# LED.net
KiCad netlist of a schematic drawn in Altium Designer
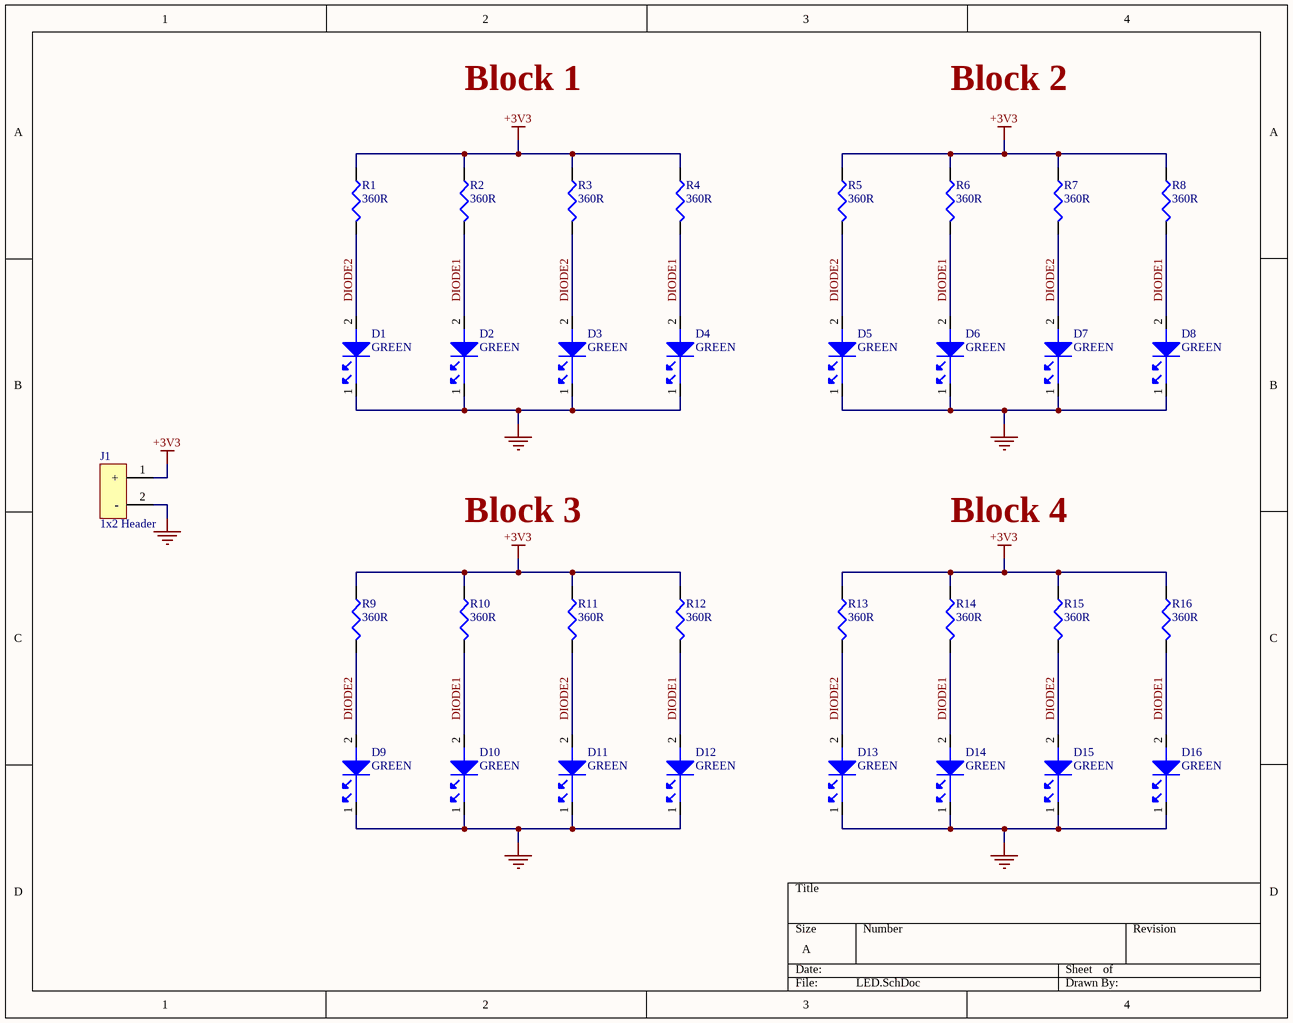
[diagram p0: LED.SchDoc]

(export (version "E")
  (design (tool "Eeschema 10.0.6"))
  (components
    (comp (ref "D1")
      (value "GREEN")
      (footprint "LED0603G")
      (description "Standard LEDs - SMD LED GR HI-BRT USS")
      (fields
        (field (name "MANUFACTURER") "Panasonic SSG")
        (field (name "MANUFACTURER PART NUMBER") "LNJ337W83RA")
      )
      (libsource (lib "LED_SchLib") (part "LNJ337W83RA"))
    )
    (comp (ref "D2")
      (value "GREEN")
      (footprint "LED0603G")
      (description "Standard LEDs - SMD LED GR HI-BRT USS")
      (fields
        (field (name "MANUFACTURER") "Panasonic SSG")
        (field (name "MANUFACTURER PART NUMBER") "LNJ337W83RA")
      )
      (libsource (lib "LED_SchLib") (part "LNJ337W83RA"))
    )
    (comp (ref "D3")
      (value "GREEN")
      (footprint "LED0603G")
      (description "Standard LEDs - SMD LED GR HI-BRT USS")
      (fields
        (field (name "MANUFACTURER") "Panasonic SSG")
        (field (name "MANUFACTURER PART NUMBER") "LNJ337W83RA")
      )
      (libsource (lib "LED_SchLib") (part "LNJ337W83RA"))
    )
    (comp (ref "D4")
      (value "GREEN")
      (footprint "LED0603G")
      (description "Standard LEDs - SMD LED GR HI-BRT USS")
      (fields
        (field (name "MANUFACTURER") "Panasonic SSG")
        (field (name "MANUFACTURER PART NUMBER") "LNJ337W83RA")
      )
      (libsource (lib "LED_SchLib") (part "LNJ337W83RA"))
    )
    (comp (ref "D5")
      (value "GREEN")
      (footprint "LED0603G")
      (description "Standard LEDs - SMD LED GR HI-BRT USS")
      (fields
        (field (name "MANUFACTURER") "Panasonic SSG")
        (field (name "MANUFACTURER PART NUMBER") "LNJ337W83RA")
      )
      (libsource (lib "LED_SchLib") (part "LNJ337W83RA"))
    )
    (comp (ref "D6")
      (value "GREEN")
      (footprint "LED0603G")
      (description "Standard LEDs - SMD LED GR HI-BRT USS")
      (fields
        (field (name "MANUFACTURER") "Panasonic SSG")
        (field (name "MANUFACTURER PART NUMBER") "LNJ337W83RA")
      )
      (libsource (lib "LED_SchLib") (part "LNJ337W83RA"))
    )
    (comp (ref "D7")
      (value "GREEN")
      (footprint "LED0603G")
      (description "Standard LEDs - SMD LED GR HI-BRT USS")
      (fields
        (field (name "MANUFACTURER") "Panasonic SSG")
        (field (name "MANUFACTURER PART NUMBER") "LNJ337W83RA")
      )
      (libsource (lib "LED_SchLib") (part "LNJ337W83RA"))
    )
    (comp (ref "D8")
      (value "GREEN")
      (footprint "LED0603G")
      (description "Standard LEDs - SMD LED GR HI-BRT USS")
      (fields
        (field (name "MANUFACTURER") "Panasonic SSG")
        (field (name "MANUFACTURER PART NUMBER") "LNJ337W83RA")
      )
      (libsource (lib "LED_SchLib") (part "LNJ337W83RA"))
    )
    (comp (ref "D9")
      (value "GREEN")
      (footprint "LED0603G")
      (description "Standard LEDs - SMD LED GR HI-BRT USS")
      (fields
        (field (name "MANUFACTURER") "Panasonic SSG")
        (field (name "MANUFACTURER PART NUMBER") "LNJ337W83RA")
      )
      (libsource (lib "LED_SchLib") (part "LNJ337W83RA"))
    )
    (comp (ref "D10")
      (value "GREEN")
      (footprint "LED0603G")
      (description "Standard LEDs - SMD LED GR HI-BRT USS")
      (fields
        (field (name "MANUFACTURER") "Panasonic SSG")
        (field (name "MANUFACTURER PART NUMBER") "LNJ337W83RA")
      )
      (libsource (lib "LED_SchLib") (part "LNJ337W83RA"))
    )
    (comp (ref "D11")
      (value "GREEN")
      (footprint "LED0603G")
      (description "Standard LEDs - SMD LED GR HI-BRT USS")
      (fields
        (field (name "MANUFACTURER") "Panasonic SSG")
        (field (name "MANUFACTURER PART NUMBER") "LNJ337W83RA")
      )
      (libsource (lib "LED_SchLib") (part "LNJ337W83RA"))
    )
    (comp (ref "D12")
      (value "GREEN")
      (footprint "LED0603G")
      (description "Standard LEDs - SMD LED GR HI-BRT USS")
      (fields
        (field (name "MANUFACTURER") "Panasonic SSG")
        (field (name "MANUFACTURER PART NUMBER") "LNJ337W83RA")
      )
      (libsource (lib "LED_SchLib") (part "LNJ337W83RA"))
    )
    (comp (ref "D13")
      (value "GREEN")
      (footprint "LED0603G")
      (description "Standard LEDs - SMD LED GR HI-BRT USS")
      (fields
        (field (name "MANUFACTURER") "Panasonic SSG")
        (field (name "MANUFACTURER PART NUMBER") "LNJ337W83RA")
      )
      (libsource (lib "LED_SchLib") (part "LNJ337W83RA"))
    )
    (comp (ref "D14")
      (value "GREEN")
      (footprint "LED0603G")
      (description "Standard LEDs - SMD LED GR HI-BRT USS")
      (fields
        (field (name "MANUFACTURER") "Panasonic SSG")
        (field (name "MANUFACTURER PART NUMBER") "LNJ337W83RA")
      )
      (libsource (lib "LED_SchLib") (part "LNJ337W83RA"))
    )
    (comp (ref "D15")
      (value "GREEN")
      (footprint "LED0603G")
      (description "Standard LEDs - SMD LED GR HI-BRT USS")
      (fields
        (field (name "MANUFACTURER") "Panasonic SSG")
        (field (name "MANUFACTURER PART NUMBER") "LNJ337W83RA")
      )
      (libsource (lib "LED_SchLib") (part "LNJ337W83RA"))
    )
    (comp (ref "D16")
      (value "GREEN")
      (footprint "LED0603G")
      (description "Standard LEDs - SMD LED GR HI-BRT USS")
      (fields
        (field (name "MANUFACTURER") "Panasonic SSG")
        (field (name "MANUFACTURER PART NUMBER") "LNJ337W83RA")
      )
      (libsource (lib "LED_SchLib") (part "LNJ337W83RA"))
    )
    (comp (ref "J1")
      (value "1x2 Header")
      (footprint "HDR1X2")
      (description "Headers & Wire Housings 2 PIN F/LK HEADER")
      (fields (field (name "MANUFACTURER") "Molex") (field (name "MANUFACTURER PART NUMBER") "22-29-2021"))
      (libsource (lib "LED_SchLib") (part "22-29-2021"))
    )
    (comp (ref "R1")
      (value "360R")
      (footprint "R0805")
      (description "RES SMD 360 OHM 1% 1/8W 0805")
      (fields
        (field (name "MANUFACTURER") "Vishay")
        (field (name "MANUFACTURER PART NUMBER") "CRCW0805360RFKEA")
      )
      (libsource (lib "LED_SchLib") (part "CRCW0805360RFKEA"))
    )
    (comp (ref "R2")
      (value "360R")
      (footprint "R0805")
      (description "RES SMD 360 OHM 1% 1/8W 0805")
      (fields
        (field (name "MANUFACTURER") "Vishay")
        (field (name "MANUFACTURER PART NUMBER") "CRCW0805360RFKEA")
      )
      (libsource (lib "LED_SchLib") (part "CRCW0805360RFKEA"))
    )
    (comp (ref "R3")
      (value "360R")
      (footprint "R0805")
      (description "RES SMD 360 OHM 1% 1/8W 0805")
      (fields
        (field (name "MANUFACTURER") "Vishay")
        (field (name "MANUFACTURER PART NUMBER") "CRCW0805360RFKEA")
      )
      (libsource (lib "LED_SchLib") (part "CRCW0805360RFKEA"))
    )
    (comp (ref "R4")
      (value "360R")
      (footprint "R0805")
      (description "RES SMD 360 OHM 1% 1/8W 0805")
      (fields
        (field (name "MANUFACTURER") "Vishay")
        (field (name "MANUFACTURER PART NUMBER") "CRCW0805360RFKEA")
      )
      (libsource (lib "LED_SchLib") (part "CRCW0805360RFKEA"))
    )
    (comp (ref "R5")
      (value "360R")
      (footprint "R0805")
      (description "RES SMD 360 OHM 1% 1/8W 0805")
      (fields
        (field (name "MANUFACTURER") "Vishay")
        (field (name "MANUFACTURER PART NUMBER") "CRCW0805360RFKEA")
      )
      (libsource (lib "LED_SchLib") (part "CRCW0805360RFKEA"))
    )
    (comp (ref "R6")
      (value "360R")
      (footprint "R0805")
      (description "RES SMD 360 OHM 1% 1/8W 0805")
      (fields
        (field (name "MANUFACTURER") "Vishay")
        (field (name "MANUFACTURER PART NUMBER") "CRCW0805360RFKEA")
      )
      (libsource (lib "LED_SchLib") (part "CRCW0805360RFKEA"))
    )
    (comp (ref "R7")
      (value "360R")
      (footprint "R0805")
      (description "RES SMD 360 OHM 1% 1/8W 0805")
      (fields
        (field (name "MANUFACTURER") "Vishay")
        (field (name "MANUFACTURER PART NUMBER") "CRCW0805360RFKEA")
      )
      (libsource (lib "LED_SchLib") (part "CRCW0805360RFKEA"))
    )
    (comp (ref "R8")
      (value "360R")
      (footprint "R0805")
      (description "RES SMD 360 OHM 1% 1/8W 0805")
      (fields
        (field (name "MANUFACTURER") "Vishay")
        (field (name "MANUFACTURER PART NUMBER") "CRCW0805360RFKEA")
      )
      (libsource (lib "LED_SchLib") (part "CRCW0805360RFKEA"))
    )
    (comp (ref "R9")
      (value "360R")
      (footprint "R0805")
      (description "RES SMD 360 OHM 1% 1/8W 0805")
      (fields
        (field (name "MANUFACTURER") "Vishay")
        (field (name "MANUFACTURER PART NUMBER") "CRCW0805360RFKEA")
      )
      (libsource (lib "LED_SchLib") (part "CRCW0805360RFKEA"))
    )
    (comp (ref "R10")
      (value "360R")
      (footprint "R0805")
      (description "RES SMD 360 OHM 1% 1/8W 0805")
      (fields
        (field (name "MANUFACTURER") "Vishay")
        (field (name "MANUFACTURER PART NUMBER") "CRCW0805360RFKEA")
      )
      (libsource (lib "LED_SchLib") (part "CRCW0805360RFKEA"))
    )
    (comp (ref "R11")
      (value "360R")
      (footprint "R0805")
      (description "RES SMD 360 OHM 1% 1/8W 0805")
      (fields
        (field (name "MANUFACTURER") "Vishay")
        (field (name "MANUFACTURER PART NUMBER") "CRCW0805360RFKEA")
      )
      (libsource (lib "LED_SchLib") (part "CRCW0805360RFKEA"))
    )
    (comp (ref "R12")
      (value "360R")
      (footprint "R0805")
      (description "RES SMD 360 OHM 1% 1/8W 0805")
      (fields
        (field (name "MANUFACTURER") "Vishay")
        (field (name "MANUFACTURER PART NUMBER") "CRCW0805360RFKEA")
      )
      (libsource (lib "LED_SchLib") (part "CRCW0805360RFKEA"))
    )
    (comp (ref "R13")
      (value "360R")
      (footprint "R0805")
      (description "RES SMD 360 OHM 1% 1/8W 0805")
      (fields
        (field (name "MANUFACTURER") "Vishay")
        (field (name "MANUFACTURER PART NUMBER") "CRCW0805360RFKEA")
      )
      (libsource (lib "LED_SchLib") (part "CRCW0805360RFKEA"))
    )
    (comp (ref "R14")
      (value "360R")
      (footprint "R0805")
      (description "RES SMD 360 OHM 1% 1/8W 0805")
      (fields
        (field (name "MANUFACTURER") "Vishay")
        (field (name "MANUFACTURER PART NUMBER") "CRCW0805360RFKEA")
      )
      (libsource (lib "LED_SchLib") (part "CRCW0805360RFKEA"))
    )
    (comp (ref "R15")
      (value "360R")
      (footprint "R0805")
      (description "RES SMD 360 OHM 1% 1/8W 0805")
      (fields
        (field (name "MANUFACTURER") "Vishay")
        (field (name "MANUFACTURER PART NUMBER") "CRCW0805360RFKEA")
      )
      (libsource (lib "LED_SchLib") (part "CRCW0805360RFKEA"))
    )
    (comp (ref "R16")
      (value "360R")
      (footprint "R0805")
      (description "RES SMD 360 OHM 1% 1/8W 0805")
      (fields
        (field (name "MANUFACTURER") "Vishay")
        (field (name "MANUFACTURER PART NUMBER") "CRCW0805360RFKEA")
      )
      (libsource (lib "LED_SchLib") (part "CRCW0805360RFKEA"))
    )
  )
  (nets
    (net (code "1") (name "+3V3") (class "Default")
      (node (ref "J1") (pin "1") (pinfunction "+_1") (pintype "passive"))
      (node (ref "R1") (pin "1") (pinfunction "1_1") (pintype "passive"))
      (node (ref "R10") (pin "1") (pinfunction "1_1") (pintype "passive"))
      (node (ref "R11") (pin "1") (pinfunction "1_1") (pintype "passive"))
      (node (ref "R12") (pin "1") (pinfunction "1_1") (pintype "passive"))
      (node (ref "R13") (pin "1") (pinfunction "1_1") (pintype "passive"))
      (node (ref "R14") (pin "1") (pinfunction "1_1") (pintype "passive"))
      (node (ref "R15") (pin "1") (pinfunction "1_1") (pintype "passive"))
      (node (ref "R16") (pin "1") (pinfunction "1_1") (pintype "passive"))
      (node (ref "R2") (pin "1") (pinfunction "1_1") (pintype "passive"))
      (node (ref "R3") (pin "1") (pinfunction "1_1") (pintype "passive"))
      (node (ref "R4") (pin "1") (pinfunction "1_1") (pintype "passive"))
      (node (ref "R5") (pin "1") (pinfunction "1_1") (pintype "passive"))
      (node (ref "R6") (pin "1") (pinfunction "1_1") (pintype "passive"))
      (node (ref "R7") (pin "1") (pinfunction "1_1") (pintype "passive"))
      (node (ref "R8") (pin "1") (pinfunction "1_1") (pintype "passive"))
      (node (ref "R9") (pin "1") (pinfunction "1_1") (pintype "passive"))
    )
    (net (code "2") (name "/DIODE1") (class "Default")
      (node (ref "D10") (pin "2") (pinfunction "2_2") (pintype "passive"))
      (node (ref "D12") (pin "2") (pinfunction "2_2") (pintype "passive"))
      (node (ref "D14") (pin "2") (pinfunction "2_2") (pintype "passive"))
      (node (ref "D16") (pin "2") (pinfunction "2_2") (pintype "passive"))
      (node (ref "D2") (pin "2") (pinfunction "2_2") (pintype "passive"))
      (node (ref "D4") (pin "2") (pinfunction "2_2") (pintype "passive"))
      (node (ref "D6") (pin "2") (pinfunction "2_2") (pintype "passive"))
      (node (ref "D8") (pin "2") (pinfunction "2_2") (pintype "passive"))
      (node (ref "R10") (pin "2") (pinfunction "2_2") (pintype "passive"))
      (node (ref "R12") (pin "2") (pinfunction "2_2") (pintype "passive"))
      (node (ref "R14") (pin "2") (pinfunction "2_2") (pintype "passive"))
      (node (ref "R16") (pin "2") (pinfunction "2_2") (pintype "passive"))
      (node (ref "R2") (pin "2") (pinfunction "2_2") (pintype "passive"))
      (node (ref "R4") (pin "2") (pinfunction "2_2") (pintype "passive"))
      (node (ref "R6") (pin "2") (pinfunction "2_2") (pintype "passive"))
      (node (ref "R8") (pin "2") (pinfunction "2_2") (pintype "passive"))
    )
    (net (code "3") (name "/DIODE2") (class "Default")
      (node (ref "D1") (pin "2") (pinfunction "2_2") (pintype "passive"))
      (node (ref "D11") (pin "2") (pinfunction "2_2") (pintype "passive"))
      (node (ref "D13") (pin "2") (pinfunction "2_2") (pintype "passive"))
      (node (ref "D15") (pin "2") (pinfunction "2_2") (pintype "passive"))
      (node (ref "D3") (pin "2") (pinfunction "2_2") (pintype "passive"))
      (node (ref "D5") (pin "2") (pinfunction "2_2") (pintype "passive"))
      (node (ref "D7") (pin "2") (pinfunction "2_2") (pintype "passive"))
      (node (ref "D9") (pin "2") (pinfunction "2_2") (pintype "passive"))
      (node (ref "R1") (pin "2") (pinfunction "2_2") (pintype "passive"))
      (node (ref "R11") (pin "2") (pinfunction "2_2") (pintype "passive"))
      (node (ref "R13") (pin "2") (pinfunction "2_2") (pintype "passive"))
      (node (ref "R15") (pin "2") (pinfunction "2_2") (pintype "passive"))
      (node (ref "R3") (pin "2") (pinfunction "2_2") (pintype "passive"))
      (node (ref "R5") (pin "2") (pinfunction "2_2") (pintype "passive"))
      (node (ref "R7") (pin "2") (pinfunction "2_2") (pintype "passive"))
      (node (ref "R9") (pin "2") (pinfunction "2_2") (pintype "passive"))
    )
    (net (code "4") (name "GND") (class "Default")
      (node (ref "D1") (pin "1") (pinfunction "1_1") (pintype "passive"))
      (node (ref "D10") (pin "1") (pinfunction "1_1") (pintype "passive"))
      (node (ref "D11") (pin "1") (pinfunction "1_1") (pintype "passive"))
      (node (ref "D12") (pin "1") (pinfunction "1_1") (pintype "passive"))
      (node (ref "D13") (pin "1") (pinfunction "1_1") (pintype "passive"))
      (node (ref "D14") (pin "1") (pinfunction "1_1") (pintype "passive"))
      (node (ref "D15") (pin "1") (pinfunction "1_1") (pintype "passive"))
      (node (ref "D16") (pin "1") (pinfunction "1_1") (pintype "passive"))
      (node (ref "D2") (pin "1") (pinfunction "1_1") (pintype "passive"))
      (node (ref "D3") (pin "1") (pinfunction "1_1") (pintype "passive"))
      (node (ref "D4") (pin "1") (pinfunction "1_1") (pintype "passive"))
      (node (ref "D5") (pin "1") (pinfunction "1_1") (pintype "passive"))
      (node (ref "D6") (pin "1") (pinfunction "1_1") (pintype "passive"))
      (node (ref "D7") (pin "1") (pinfunction "1_1") (pintype "passive"))
      (node (ref "D8") (pin "1") (pinfunction "1_1") (pintype "passive"))
      (node (ref "D9") (pin "1") (pinfunction "1_1") (pintype "passive"))
      (node (ref "J1") (pin "2") (pinfunction "-_2") (pintype "passive"))
    )
  )
)
